# serial-receiver.net
KiCad netlist of a schematic drawn in EAGLE
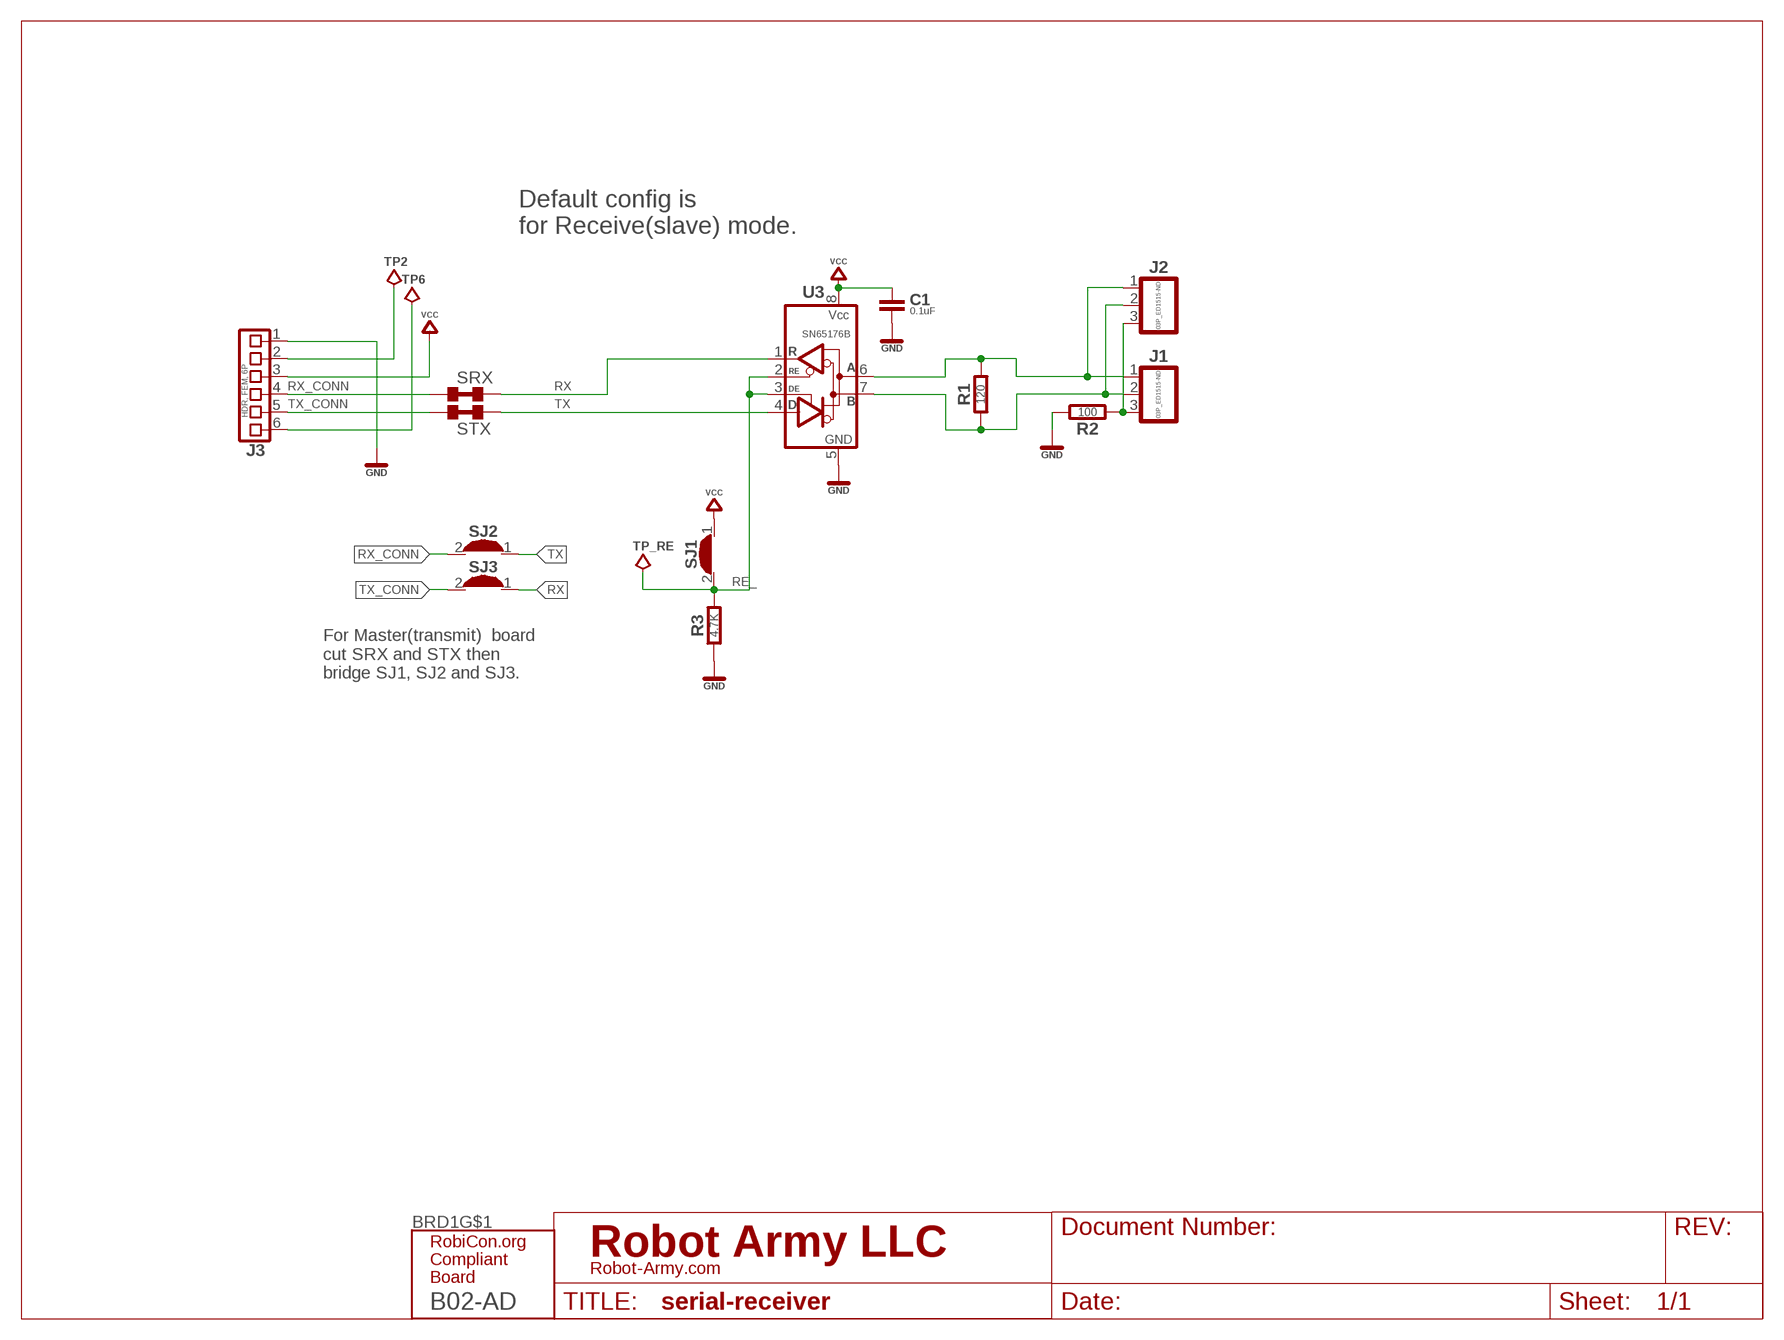
[diagram p0: schematic, sheet 1]

(export (version "E")
  (design (tool "Eeschema 10.0.6"))
  (components
    (comp (ref "BRD1")
      (value "B02-AD")
      (footprint "eagle-import:B02-AD")
      (libsource (lib "eagle-import") (part "BRD-?-ADB02"))
    )
    (comp (ref "C1")
      (value "0.1uF")
      (footprint "eagle-import:0603")
      (libsource (lib "eagle-import") (part "CAPACITOR0603"))
    )
    (comp (ref "J1")
      (value "03P_ED1515-ND")
      (footprint "eagle-import:TB35-03")
      (libsource (lib "eagle-import") (part "03P_ED1515-ND"))
    )
    (comp (ref "J2")
      (value "03P_ED1515-ND")
      (footprint "eagle-import:TB35-03")
      (libsource (lib "eagle-import") (part "03P_ED1515-ND"))
    )
    (comp (ref "J3")
      (value "HDR, FEM, 6P")
      (footprint "eagle-import:FE06")
      (libsource (lib "eagle-import") (part "FE06-1"))
    )
    (comp (ref "R1")
      (value "120")
      (footprint "eagle-import:1206")
      (libsource (lib "eagle-import") (part "RESISTOR1206"))
    )
    (comp (ref "R2")
      (value "100")
      (footprint "eagle-import:1206")
      (libsource (lib "eagle-import") (part "RESISTOR1206"))
    )
    (comp (ref "R3")
      (value "4.7K")
      (footprint "eagle-import:0603")
      (libsource (lib "eagle-import") (part "RESISTOR0603"))
    )
    (comp (ref "SJ1")
      (value "SOLDER_JUMPER")
      (footprint "eagle-import:SOLDER_JUMP")
      (libsource (lib "eagle-import") (part "SOLDER_JUMPER"))
    )
    (comp (ref "SJ2")
      (value "SOLDER_JUMPER")
      (footprint "eagle-import:SOLDER_JUMP")
      (libsource (lib "eagle-import") (part "SOLDER_JUMPER"))
    )
    (comp (ref "SJ3")
      (value "SOLDER_JUMPER")
      (footprint "eagle-import:SOLDER_JUMP")
      (libsource (lib "eagle-import") (part "SOLDER_JUMPER"))
    )
    (comp (ref "SRX")
      (value "SHORT0603")
      (footprint "eagle-import:0603-SHORT")
      (libsource (lib "eagle-import") (part "SHORT0603"))
    )
    (comp (ref "STX")
      (value "SHORT0603")
      (footprint "eagle-import:0603-SHORT")
      (libsource (lib "eagle-import") (part "SHORT0603"))
    )
    (comp (ref "TP2")
      (value "TEST_POINT_SM_2X2")
      (footprint "eagle-import:TP-SMT-020X020")
      (libsource (lib "eagle-import") (part "TEST_POINT_SM_2X2"))
    )
    (comp (ref "TP6")
      (value "TEST_POINT_SM_2X2")
      (footprint "eagle-import:TP-SMT-020X020")
      (libsource (lib "eagle-import") (part "TEST_POINT_SM_2X2"))
    )
    (comp (ref "TP_RE")
      (value "TEST_POINT_SM_2X2")
      (footprint "eagle-import:TP-SMT-020X020")
      (libsource (lib "eagle-import") (part "TEST_POINT_SM_2X2"))
    )
    (comp (ref "U3")
      (value "SN65176B")
      (footprint "eagle-import:SOP08")
      (libsource (lib "eagle-import") (part "RS485_TRANSCEIVERSO8"))
    )
  )
  (nets
    (net (code "1") (name "/RE_") (class "Default")
      (node (ref "R3") (pin "2") (pinfunction "2_2") (pintype "passive"))
      (node (ref "SJ1") (pin "2") (pinfunction "P$2_2") (pintype "passive"))
      (node (ref "TP_RE") (pin "1") (pinfunction "P$1_1") (pintype "bidirectional"))
      (node (ref "U3") (pin "2") (pinfunction "RE_2") (pintype "input"))
      (node (ref "U3") (pin "3") (pinfunction "DE_3") (pintype "input"))
    )
    (net (code "2") (name "GND") (class "Default")
      (node (ref "C1") (pin "2") (pinfunction "2_2") (pintype "passive"))
      (node (ref "J3") (pin "1") (pinfunction "1_1") (pintype "passive"))
      (node (ref "R2") (pin "1") (pinfunction "1_1") (pintype "passive"))
      (node (ref "R3") (pin "1") (pinfunction "1_1") (pintype "passive"))
      (node (ref "U3") (pin "5") (pinfunction "GND_5") (pintype "power_in"))
    )
    (net (code "3") (name "Net-(J1-Pad3)") (class "Default")
      (node (ref "J1") (pin "3") (pinfunction "3_3") (pintype "bidirectional"))
      (node (ref "J2") (pin "3") (pinfunction "3_3") (pintype "bidirectional"))
      (node (ref "R2") (pin "2") (pinfunction "2_2") (pintype "passive"))
    )
    (net (code "4") (name "Net-(TP2-P$1)") (class "Default")
      (node (ref "J3") (pin "2") (pinfunction "2_2") (pintype "passive"))
      (node (ref "TP2") (pin "1") (pinfunction "P$1_1") (pintype "bidirectional"))
    )
    (net (code "5") (name "Net-(TP6-P$1)") (class "Default")
      (node (ref "J3") (pin "6") (pinfunction "6_6") (pintype "passive"))
      (node (ref "TP6") (pin "1") (pinfunction "P$1_1") (pintype "bidirectional"))
    )
    (net (code "6") (name "Net-(U3-A)") (class "Default")
      (node (ref "J1") (pin "1") (pinfunction "1_1") (pintype "bidirectional"))
      (node (ref "J2") (pin "1") (pinfunction "1_1") (pintype "bidirectional"))
      (node (ref "R1") (pin "2") (pinfunction "2_2") (pintype "passive"))
      (node (ref "U3") (pin "6") (pinfunction "A_6") (pintype "bidirectional"))
    )
    (net (code "7") (name "Net-(U3-B)") (class "Default")
      (node (ref "J1") (pin "2") (pinfunction "2_2") (pintype "bidirectional"))
      (node (ref "J2") (pin "2") (pinfunction "2_2") (pintype "bidirectional"))
      (node (ref "R1") (pin "1") (pinfunction "1_1") (pintype "passive"))
      (node (ref "U3") (pin "7") (pinfunction "B_7") (pintype "bidirectional"))
    )
    (net (code "8") (name "RX") (class "Default")
      (node (ref "SJ3") (pin "1") (pinfunction "P$1_1") (pintype "passive"))
      (node (ref "SRX") (pin "2") (pinfunction "2_2") (pintype "passive"))
      (node (ref "U3") (pin "1") (pinfunction "R_1") (pintype "output"))
    )
    (net (code "9") (name "RX_CONN") (class "Default")
      (node (ref "J3") (pin "4") (pinfunction "4_4") (pintype "passive"))
      (node (ref "SJ2") (pin "2") (pinfunction "P$2_2") (pintype "passive"))
      (node (ref "SRX") (pin "1") (pinfunction "1_1") (pintype "passive"))
    )
    (net (code "10") (name "TX") (class "Default")
      (node (ref "SJ2") (pin "1") (pinfunction "P$1_1") (pintype "passive"))
      (node (ref "STX") (pin "2") (pinfunction "2_2") (pintype "passive"))
      (node (ref "U3") (pin "4") (pinfunction "D_4") (pintype "input"))
    )
    (net (code "11") (name "TX_CONN") (class "Default")
      (node (ref "J3") (pin "5") (pinfunction "5_5") (pintype "passive"))
      (node (ref "SJ3") (pin "2") (pinfunction "P$2_2") (pintype "passive"))
      (node (ref "STX") (pin "1") (pinfunction "1_1") (pintype "passive"))
    )
    (net (code "12") (name "VCC") (class "Default")
      (node (ref "C1") (pin "1") (pinfunction "1_1") (pintype "passive"))
      (node (ref "J3") (pin "3") (pinfunction "3_3") (pintype "passive"))
      (node (ref "SJ1") (pin "1") (pinfunction "P$1_1") (pintype "passive"))
      (node (ref "U3") (pin "8") (pinfunction "VCC_8") (pintype "power_in"))
    )
  )
)
